# Peripherals.net
KiCad netlist of a schematic drawn in Altium Designer
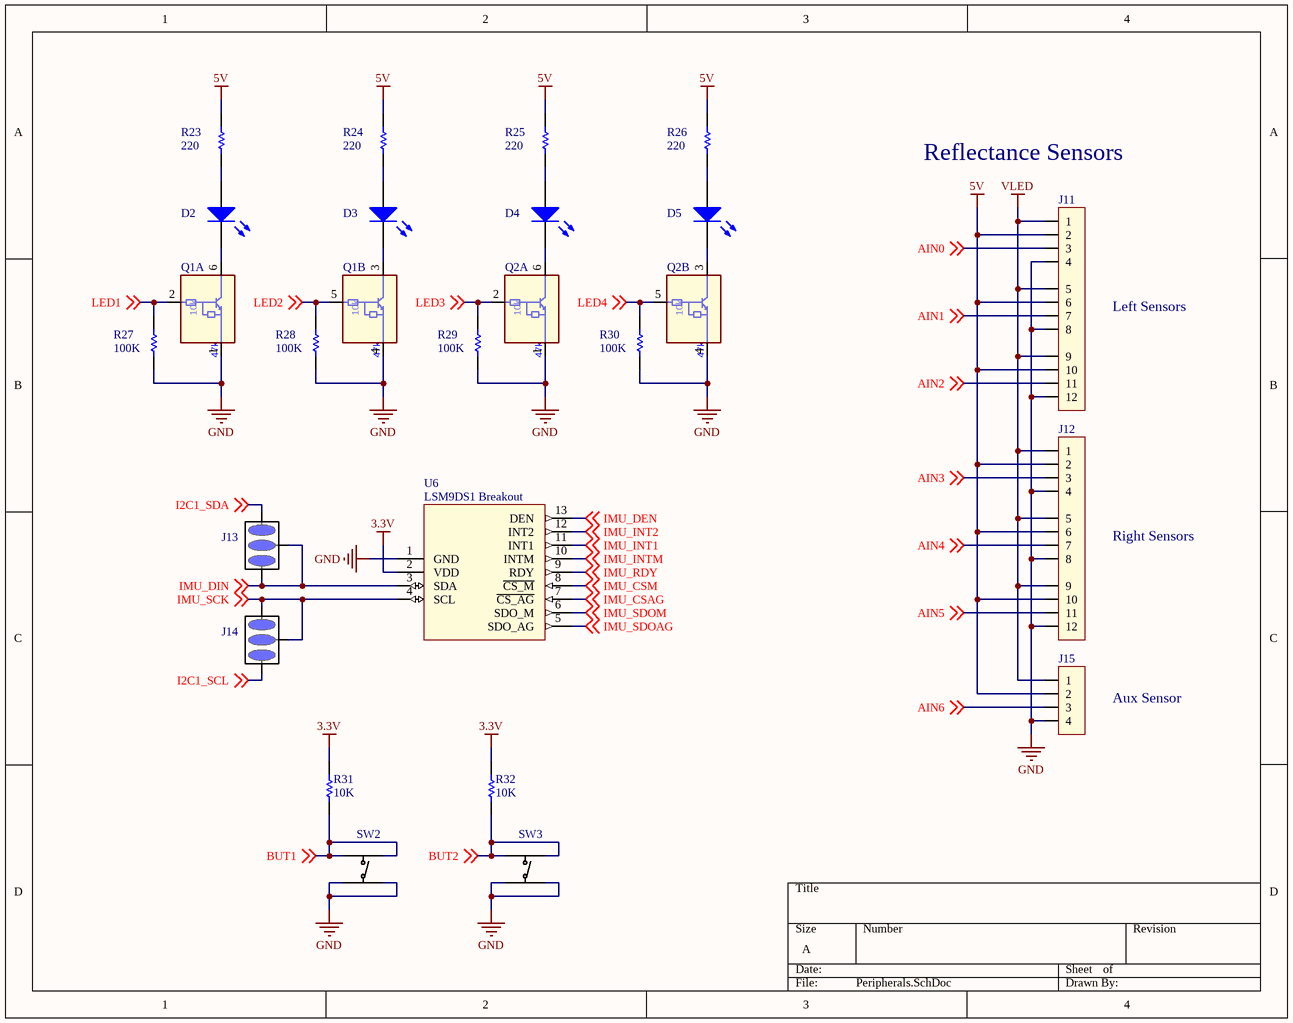
[diagram p0: Peripherals.SchDoc]

(export (version "E")
  (design (tool "Eeschema 10.0.6"))
  (components
    (comp (ref "D2")
      (value "LED")
      (footprint "0603-DI-GREEN")
      (description "LED BLUE CLEAR CHIP SMD")
      (fields (field (name "PUBLISHER") "Altium Limited"))
      (libsource (lib "MicromouseLib") (part "LED"))
    )
    (comp (ref "D3")
      (value "LED")
      (footprint "0603-DI-GREEN")
      (description "LED BLUE CLEAR CHIP SMD")
      (fields (field (name "PUBLISHER") "Altium Limited"))
      (libsource (lib "MicromouseLib") (part "LED"))
    )
    (comp (ref "D4")
      (value "LED")
      (footprint "0603-DI-GREEN")
      (description "LED BLUE CLEAR CHIP SMD")
      (fields (field (name "PUBLISHER") "Altium Limited"))
      (libsource (lib "MicromouseLib") (part "LED"))
    )
    (comp (ref "D5")
      (value "LED")
      (footprint "0603-DI-GREEN")
      (description "LED BLUE CLEAR CHIP SMD")
      (fields (field (name "PUBLISHER") "Altium Limited"))
      (libsource (lib "MicromouseLib") (part "LED"))
    )
    (comp (ref "J11")
      (value "CONN_4x3")
      (footprint "CONN_4x3")
      (description "CONN HEADER R/A 12POS 2.54MM")
      (libsource (lib "MicromouseLib") (part "CONN_4x3"))
    )
    (comp (ref "J12")
      (value "CONN_4x3")
      (footprint "CONN_4x3")
      (description "CONN HEADER R/A 12POS 2.54MM")
      (libsource (lib "MicromouseLib") (part "CONN_4x3"))
    )
    (comp (ref "J13")
      (value "JUMPER_3")
      (footprint "JUMPER_3")
      (libsource (lib "MicromouseLib") (part "JUMPER_3"))
    )
    (comp (ref "J14")
      (value "JUMPER_3")
      (footprint "JUMPER_3")
      (libsource (lib "MicromouseLib") (part "JUMPER_3"))
    )
    (comp (ref "J15")
      (value "CONN_4x1")
      (footprint "HDR1X4")
      (libsource (lib "MicromouseLib") (part "CONN_4x1"))
    )
    (comp (ref "Q1")
      (value "RN1907")
      (footprint "SOT363-6L")
      (description "TRANS 2NPN PREBIAS 0.2W US6")
      (libsource (lib "MicromouseLib") (part "RN1907"))
    )
    (comp (ref "Q2")
      (value "RN1907")
      (footprint "SOT363-6L")
      (description "TRANS 2NPN PREBIAS 0.2W US6")
      (libsource (lib "MicromouseLib") (part "RN1907"))
    )
    (comp (ref "R23")
      (value "220")
      (footprint "J1-0603")
      (description "RES SMD 220 OHM 5% 1/10W 0603")
      (libsource (lib "Miscellaneous Devices") (part "Res1"))
    )
    (comp (ref "R24")
      (value "220")
      (footprint "J1-0603")
      (description "RES SMD 220 OHM 5% 1/10W 0603")
      (libsource (lib "Miscellaneous Devices") (part "Res1"))
    )
    (comp (ref "R25")
      (value "220")
      (footprint "J1-0603")
      (description "RES SMD 220 OHM 5% 1/10W 0603")
      (libsource (lib "Miscellaneous Devices") (part "Res1"))
    )
    (comp (ref "R26")
      (value "220")
      (footprint "J1-0603")
      (description "RES SMD 220 OHM 5% 1/10W 0603")
      (libsource (lib "Miscellaneous Devices") (part "Res1"))
    )
    (comp (ref "R27")
      (value "100K")
      (footprint "J1-0603")
      (description "RES SMD 100K OHM 5% 1/10W 0603")
      (libsource (lib "Miscellaneous Devices") (part "Res1"))
    )
    (comp (ref "R28")
      (value "100K")
      (footprint "J1-0603")
      (description "RES SMD 100K OHM 5% 1/10W 0603")
      (libsource (lib "Miscellaneous Devices") (part "Res1"))
    )
    (comp (ref "R29")
      (value "100K")
      (footprint "J1-0603")
      (description "RES SMD 100K OHM 5% 1/10W 0603")
      (libsource (lib "Miscellaneous Devices") (part "Res1"))
    )
    (comp (ref "R30")
      (value "100K")
      (footprint "J1-0603")
      (description "RES SMD 100K OHM 5% 1/10W 0603")
      (libsource (lib "Miscellaneous Devices") (part "Res1"))
    )
    (comp (ref "R31")
      (value "10K")
      (footprint "J1-0603")
      (description "RES SMD 10K OHM 5% 1/10W 0603")
      (libsource (lib "Miscellaneous Devices") (part "Res1"))
    )
    (comp (ref "R32")
      (value "10K")
      (footprint "J1-0603")
      (description "RES SMD 10K OHM 5% 1/10W 0603")
      (libsource (lib "Miscellaneous Devices") (part "Res1"))
    )
    (comp (ref "SW2")
      (value "TACT SWITCH")
      (footprint "TACT SWITCH")
      (description "SWITCH TACTILE SPST-NO 0.05A 12V")
      (fields
        (field (name "MANUFACTURER") "C&K")
        (field (name "MANUFACTURER PART NUMBER") "PTS645SL50SMTR92 LFS")
      )
      (libsource (lib "MicromouseLib") (part "TACT SWITCH"))
    )
    (comp (ref "SW3")
      (value "TACT SWITCH")
      (footprint "TACT SWITCH")
      (description "SWITCH TACTILE SPST-NO 0.05A 12V")
      (fields
        (field (name "MANUFACTURER") "C&K")
        (field (name "MANUFACTURER PART NUMBER") "PTS645SL50SMTR92 LFS")
      )
      (libsource (lib "MicromouseLib") (part "TACT SWITCH"))
    )
    (comp (ref "U6")
      (value "LSM9DS1 Breakout")
      (footprint "LSM9DS1 Breakout")
      (description "SPARKFUN 9 DEGREES OF FREEDOM IM")
      (libsource (lib "MicromouseLib") (part "LSM9DS1 Breakout"))
    )
  )
  (nets
    (net (code "1") (name "3.3V") (class "Default")
      (node (ref "R31") (pin "1") (pinfunction "1_1") (pintype "passive"))
      (node (ref "R32") (pin "1") (pinfunction "1_1") (pintype "passive"))
      (node (ref "U6") (pin "2") (pinfunction "VDD_2") (pintype "power_in"))
    )
    (net (code "2") (name "5V") (class "Default")
      (node (ref "J11") (pin "10") (pinfunction "10_10") (pintype "passive"))
      (node (ref "J11") (pin "2") (pinfunction "2_2") (pintype "passive"))
      (node (ref "J11") (pin "6") (pinfunction "6_6") (pintype "passive"))
      (node (ref "J12") (pin "10") (pinfunction "10_10") (pintype "passive"))
      (node (ref "J12") (pin "2") (pinfunction "2_2") (pintype "passive"))
      (node (ref "J12") (pin "6") (pinfunction "6_6") (pintype "passive"))
      (node (ref "J15") (pin "2") (pinfunction "2_2") (pintype "passive"))
      (node (ref "R23") (pin "2") (pinfunction "2_2") (pintype "passive"))
      (node (ref "R24") (pin "2") (pinfunction "2_2") (pintype "passive"))
      (node (ref "R25") (pin "2") (pinfunction "2_2") (pintype "passive"))
      (node (ref "R26") (pin "2") (pinfunction "2_2") (pintype "passive"))
    )
    (net (code "3") (name "AIN0") (class "Default")
      (node (ref "J11") (pin "3") (pinfunction "3_3") (pintype "passive"))
    )
    (net (code "4") (name "AIN1") (class "Default")
      (node (ref "J11") (pin "7") (pinfunction "7_7") (pintype "passive"))
    )
    (net (code "5") (name "AIN2") (class "Default")
      (node (ref "J11") (pin "11") (pinfunction "11_11") (pintype "passive"))
    )
    (net (code "6") (name "AIN3") (class "Default")
      (node (ref "J12") (pin "3") (pinfunction "3_3") (pintype "passive"))
    )
    (net (code "7") (name "AIN4") (class "Default")
      (node (ref "J12") (pin "7") (pinfunction "7_7") (pintype "passive"))
    )
    (net (code "8") (name "AIN5") (class "Default")
      (node (ref "J12") (pin "11") (pinfunction "11_11") (pintype "passive"))
    )
    (net (code "9") (name "AIN6") (class "Default")
      (node (ref "J15") (pin "3") (pinfunction "3_3") (pintype "passive"))
    )
    (net (code "10") (name "BUT1") (class "Default")
      (node (ref "R31") (pin "2") (pinfunction "2_2") (pintype "passive"))
      (node (ref "SW2") (pin "1") (pintype "power_in"))
      (node (ref "SW2") (pin "2") (pintype "power_in"))
    )
    (net (code "11") (name "BUT2") (class "Default")
      (node (ref "R32") (pin "2") (pinfunction "2_2") (pintype "passive"))
      (node (ref "SW3") (pin "1") (pintype "power_in"))
      (node (ref "SW3") (pin "2") (pintype "power_in"))
    )
    (net (code "12") (name "GND") (class "Default")
      (node (ref "J11") (pin "12") (pinfunction "12_12") (pintype "passive"))
      (node (ref "J11") (pin "4") (pinfunction "4_4") (pintype "passive"))
      (node (ref "J11") (pin "8") (pinfunction "8_8") (pintype "passive"))
      (node (ref "J12") (pin "12") (pinfunction "12_12") (pintype "passive"))
      (node (ref "J12") (pin "4") (pinfunction "4_4") (pintype "passive"))
      (node (ref "J12") (pin "8") (pinfunction "8_8") (pintype "passive"))
      (node (ref "J15") (pin "4") (pinfunction "4_4") (pintype "passive"))
      (node (ref "Q1") (pin "1") (pinfunction "4_1") (pintype "passive"))
      (node (ref "Q1") (pin "4") (pinfunction "4_4") (pintype "passive"))
      (node (ref "Q2") (pin "1") (pinfunction "4_1") (pintype "passive"))
      (node (ref "Q2") (pin "4") (pinfunction "4_4") (pintype "passive"))
      (node (ref "R27") (pin "1") (pinfunction "1_1") (pintype "passive"))
      (node (ref "R28") (pin "1") (pinfunction "1_1") (pintype "passive"))
      (node (ref "R29") (pin "1") (pinfunction "1_1") (pintype "passive"))
      (node (ref "R30") (pin "1") (pinfunction "1_1") (pintype "passive"))
      (node (ref "SW2") (pin "3") (pintype "power_in"))
      (node (ref "SW2") (pin "4") (pintype "power_in"))
      (node (ref "SW3") (pin "3") (pintype "power_in"))
      (node (ref "SW3") (pin "4") (pintype "power_in"))
      (node (ref "U6") (pin "1") (pinfunction "GND_1") (pintype "power_in"))
    )
    (net (code "13") (name "I2C1_SCL") (class "Default") (node (ref "J14") (pin "1") (pintype "power_in")))
    (net (code "14") (name "I2C1_SDA") (class "Default") (node (ref "J13") (pin "3") (pintype "power_in")))
    (net (code "15") (name "IMU_CSAG") (class "Default")
      (node (ref "U6") (pin "7") (pinfunction "~{CS_AG}_7") (pintype "input"))
    )
    (net (code "16") (name "IMU_CSM") (class "Default")
      (node (ref "U6") (pin "8") (pinfunction "~{CS_M}_8") (pintype "input"))
    )
    (net (code "17") (name "IMU_DEN") (class "Default")
      (node (ref "U6") (pin "13") (pinfunction "DEN_13") (pintype "output"))
    )
    (net (code "18") (name "IMU_DIN") (class "Default")
      (node (ref "J13") (pin "1") (pintype "power_in"))
      (node (ref "J13") (pin "2") (pintype "power_in"))
      (node (ref "U6") (pin "3") (pinfunction "SDA_3") (pintype "bidirectional"))
    )
    (net (code "19") (name "IMU_INT1") (class "Default")
      (node (ref "U6") (pin "11") (pinfunction "INT1_11") (pintype "output"))
    )
    (net (code "20") (name "IMU_INT2") (class "Default")
      (node (ref "U6") (pin "12") (pinfunction "INT2_12") (pintype "output"))
    )
    (net (code "21") (name "IMU_INTM") (class "Default")
      (node (ref "U6") (pin "10") (pinfunction "INTM_10") (pintype "output"))
    )
    (net (code "22") (name "IMU_RDY") (class "Default")
      (node (ref "U6") (pin "9") (pinfunction "RDY_9") (pintype "output"))
    )
    (net (code "23") (name "IMU_SCK") (class "Default")
      (node (ref "J14") (pin "2") (pintype "power_in"))
      (node (ref "J14") (pin "3") (pintype "power_in"))
      (node (ref "U6") (pin "4") (pinfunction "SCL_4") (pintype "bidirectional"))
    )
    (net (code "24") (name "IMU_SDOAG") (class "Default")
      (node (ref "U6") (pin "5") (pinfunction "SDO_AG_5") (pintype "output"))
    )
    (net (code "25") (name "IMU_SDOM") (class "Default")
      (node (ref "U6") (pin "6") (pinfunction "SDO_M_6") (pintype "output"))
    )
    (net (code "26") (name "LED1") (class "Default")
      (node (ref "Q1") (pin "2") (pinfunction "5_2") (pintype "passive"))
      (node (ref "R27") (pin "2") (pinfunction "2_2") (pintype "passive"))
    )
    (net (code "27") (name "LED2") (class "Default")
      (node (ref "Q1") (pin "5") (pinfunction "5_5") (pintype "passive"))
      (node (ref "R28") (pin "2") (pinfunction "2_2") (pintype "passive"))
    )
    (net (code "28") (name "LED3") (class "Default")
      (node (ref "Q2") (pin "2") (pinfunction "5_2") (pintype "passive"))
      (node (ref "R29") (pin "2") (pinfunction "2_2") (pintype "passive"))
    )
    (net (code "29") (name "LED4") (class "Default")
      (node (ref "Q2") (pin "5") (pinfunction "5_5") (pintype "passive"))
      (node (ref "R30") (pin "2") (pinfunction "2_2") (pintype "passive"))
    )
    (net (code "30") (name "Net-(D2-A)") (class "Default")
      (node (ref "D2") (pin "1") (pinfunction "A_1") (pintype "passive"))
      (node (ref "R23") (pin "1") (pinfunction "1_1") (pintype "passive"))
    )
    (net (code "31") (name "Net-(D2-K)") (class "Default")
      (node (ref "D2") (pin "2") (pinfunction "K_2") (pintype "passive"))
      (node (ref "Q1") (pin "6") (pinfunction "3_6") (pintype "passive"))
    )
    (net (code "32") (name "Net-(D3-A)") (class "Default")
      (node (ref "D3") (pin "1") (pinfunction "A_1") (pintype "passive"))
      (node (ref "R24") (pin "1") (pinfunction "1_1") (pintype "passive"))
    )
    (net (code "33") (name "Net-(D3-K)") (class "Default")
      (node (ref "D3") (pin "2") (pinfunction "K_2") (pintype "passive"))
      (node (ref "Q1") (pin "3") (pinfunction "3_3") (pintype "passive"))
    )
    (net (code "34") (name "Net-(D4-A)") (class "Default")
      (node (ref "D4") (pin "1") (pinfunction "A_1") (pintype "passive"))
      (node (ref "R25") (pin "1") (pinfunction "1_1") (pintype "passive"))
    )
    (net (code "35") (name "Net-(D4-K)") (class "Default")
      (node (ref "D4") (pin "2") (pinfunction "K_2") (pintype "passive"))
      (node (ref "Q2") (pin "6") (pinfunction "3_6") (pintype "passive"))
    )
    (net (code "36") (name "Net-(D5-A)") (class "Default")
      (node (ref "D5") (pin "1") (pinfunction "A_1") (pintype "passive"))
      (node (ref "R26") (pin "1") (pinfunction "1_1") (pintype "passive"))
    )
    (net (code "37") (name "Net-(D5-K)") (class "Default")
      (node (ref "D5") (pin "2") (pinfunction "K_2") (pintype "passive"))
      (node (ref "Q2") (pin "3") (pinfunction "3_3") (pintype "passive"))
    )
    (net (code "38") (name "VLED") (class "Default")
      (node (ref "J11") (pin "1") (pinfunction "1_1") (pintype "passive"))
      (node (ref "J11") (pin "5") (pinfunction "5_5") (pintype "passive"))
      (node (ref "J11") (pin "9") (pinfunction "9_9") (pintype "passive"))
      (node (ref "J12") (pin "1") (pinfunction "1_1") (pintype "passive"))
      (node (ref "J12") (pin "5") (pinfunction "5_5") (pintype "passive"))
      (node (ref "J12") (pin "9") (pinfunction "9_9") (pintype "passive"))
      (node (ref "J15") (pin "1") (pinfunction "1_1") (pintype "passive"))
    )
  )
)
